# PCB_Reflow_Arduino_V1_0.net
KiCad netlist of a schematic drawn in Altium Designer
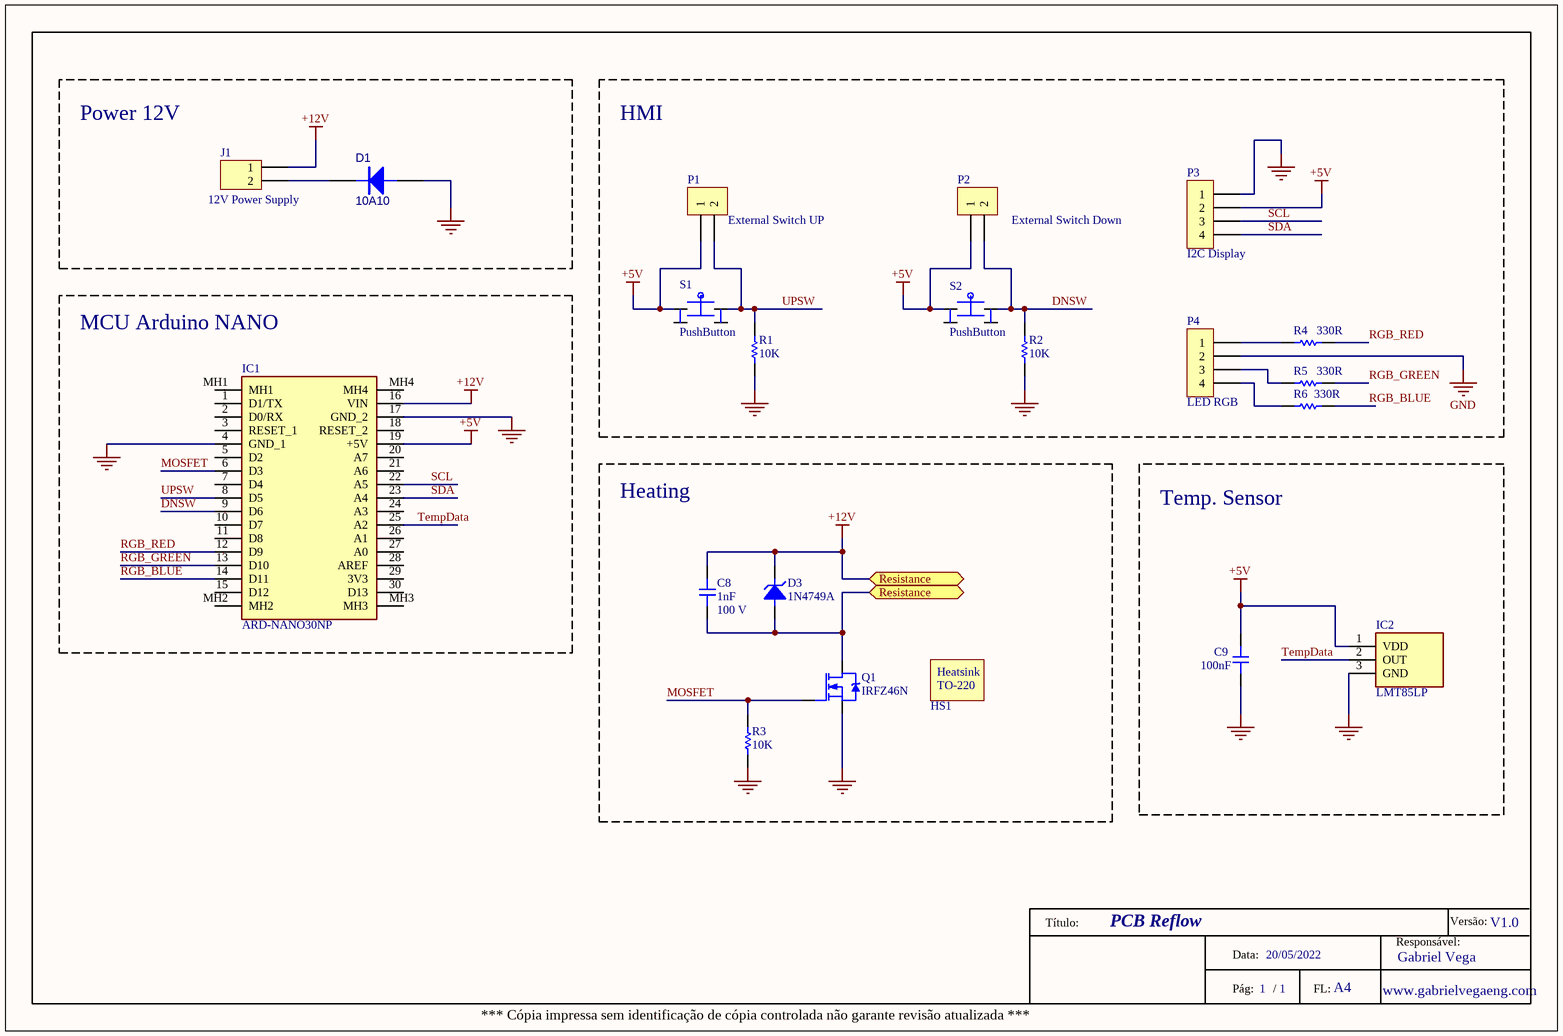
[diagram p0: PCB_Reflow_Arduino_V1.0.SchDoc]

(export (version "E")
  (design (tool "Eeschema 10.0.6"))
  (components
    (comp (ref "C8")
      (value "1nF")
      (footprint "C100-200-100")
      (description "Capacitor")
      (fields (field (name "VOLTAGE") "100 V") (field (name "PUBLISHER") "Altium Limited"))
      (libsource (lib "GPDSE_discrete") (part "Capacitor"))
    )
    (comp (ref "C9")
      (value "100nF")
      (footprint "C100-200-100")
      (description "Capacitor")
      (fields (field (name "VOLTAGE") "100 V") (field (name "PUBLISHER") "Altium Limited"))
      (libsource (lib "GPDSE_discrete") (part "Capacitor"))
    )
    (comp (ref "D1")
      (value "10A10")
      (footprint "DIODE-8.6")
      (description "Diodo")
      (libsource (lib "GPDSE_diode") (part "10A10"))
    )
    (comp (ref "D3")
      (value "1N4749A")
      (footprint "DO-41-Glass")
      (description "Zener Diode")
      (libsource (lib "GPDSE_diode") (part "1N4749A"))
    )
    (comp (ref "HS1")
      (value "HS-TO-220")
      (footprint "HS-TO-220-180847")
      (description "Heatsink TO-220")
      (libsource (lib "GPDSE") (part "HS-TO-220"))
    )
    (comp (ref "IC1")
      (value "ARD-NANO30NP")
      (footprint "SamacSys:ARDNANO30NP")
      (description "Integrated Circuit")
      (fields (field (name "MOUSER PART NUMBER") "992-ARD-NANO30NP"))
      (libsource (lib "*") (part "ARD-NANO30NP"))
    )
    (comp (ref "IC2")
      (value "LMT85LP")
      (footprint "SamacSys:LMT85LP")
      (description "Integrated Circuit")
      (fields (field (name "MOUSER PART NUMBER") "595-LMT85LP"))
      (libsource (lib "*") (part "LMT85LP"))
    )
    (comp (ref "J1")
      (value "12V Power Supply")
      (footprint "PHOENIX_1X2 - 180°")
      (description "Phoenix connector, 1 Lines, 2 Columns, 2 Pins")
      (libsource (lib "GDPSE_connector") (part "Phoenix_1x2"))
    )
    (comp (ref "P1")
      (value "External Switch UP")
      (footprint "HDR-M-1x2-2.54mm-180-9.2mm")
      (description "Header, 1 Line, 2 Columns, 2 Pins")
      (fields (field (name "PUBLISHER") "Altium Limited"))
      (libsource (lib "GDPSE_connector") (part "Header_1x2"))
    )
    (comp (ref "P2")
      (value "External Switch Down")
      (footprint "HDR-M-1x2-2.54mm-180-9.2mm")
      (description "Header, 1 Line, 2 Columns, 2 Pins")
      (fields (field (name "PUBLISHER") "Altium Limited"))
      (libsource (lib "GDPSE_connector") (part "Header_1x2"))
    )
    (comp (ref "P3")
      (value "I2C Display")
      (footprint "HDR-M-1x4-2.54mm-180-9.2mm")
      (description "Header, 1 Line, 4 Columns, 4 Pins")
      (fields (field (name "PUBLISHER") "Altium Limited"))
      (libsource (lib "GDPSE_connector") (part "Header_1x4"))
    )
    (comp (ref "P4")
      (value "LED RGB")
      (footprint "HDR-M-1x4-2.54mm-180-9.2mm")
      (description "Header, 1 Line, 4 Columns, 4 Pins")
      (fields (field (name "PUBLISHER") "Altium Limited"))
      (libsource (lib "GDPSE_connector") (part "Header_1x4"))
    )
    (comp (ref "Q1")
      (value "IRFZ46N")
      (footprint "TO-220/123")
      (description "HEXFET Power MOSFET")
      (libsource (lib "GPDSE") (part "IRFZ46N"))
    )
    (comp (ref "R1")
      (value "10K")
      (footprint "R400-2.0mm")
      (description "Resistor")
      (fields
        (field (name "TOLERANCE") "5%")
        (field (name "POWER") "1/4 W")
        (field (name "PUBLISHER") "Altium Limited")
      )
      (libsource (lib "GPDSE") (part "Resistor"))
    )
    (comp (ref "R2")
      (value "10K")
      (footprint "R400-2.0mm")
      (description "Resistor")
      (fields
        (field (name "TOLERANCE") "5%")
        (field (name "POWER") "1/4 W")
        (field (name "PUBLISHER") "Altium Limited")
      )
      (libsource (lib "GPDSE") (part "Resistor"))
    )
    (comp (ref "R3")
      (value "10K")
      (footprint "R400-2.0mm")
      (description "Resistor")
      (fields
        (field (name "TOLERANCE") "5%")
        (field (name "POWER") "1/4 W")
        (field (name "PUBLISHER") "Altium Limited")
      )
      (libsource (lib "GPDSE") (part "Resistor"))
    )
    (comp (ref "R4")
      (value "330R")
      (footprint "R400-2.0mm")
      (description "Resistor")
      (fields (field (name "TOLERANCE") "5%") (field (name "PUBLISHER") "Altium Limited"))
      (libsource (lib "GPDSE") (part "Resistor"))
    )
    (comp (ref "R5")
      (value "330R")
      (footprint "R400-2.0mm")
      (description "Resistor")
      (fields (field (name "TOLERANCE") "5%") (field (name "PUBLISHER") "Altium Limited"))
      (libsource (lib "GPDSE") (part "Resistor"))
    )
    (comp (ref "R6")
      (value "330R")
      (footprint "R400-2.0mm")
      (description "Resistor")
      (fields (field (name "TOLERANCE") "5%") (field (name "PUBLISHER") "Altium Limited"))
      (libsource (lib "GPDSE") (part "Resistor"))
    )
    (comp (ref "S1")
      (value "PushButton")
      (footprint "DTS-6.0mm-6.0mm-THT")
      (description "Tactile Switch SPST 4 pins")
      (libsource (lib "") (part "PushButton_4_1"))
    )
    (comp (ref "S2")
      (value "PushButton")
      (footprint "DTS-6.0mm-6.0mm-THT")
      (description "Tactile Switch SPST 4 pins")
      (libsource (lib "GPDSE_discrete") (part "PushButton_4"))
    )
  )
  (nets
    (net (code "1") (name "+5V") (class "Default")
      (node (ref "C9") (pin "2") (pinfunction "2_2") (pintype "passive"))
      (node (ref "IC1") (pin "19") (pinfunction "+5V_19") (pintype "passive"))
      (node (ref "IC2") (pin "1") (pinfunction "VDD_1") (pintype "passive"))
      (node (ref "P1") (pin "1") (pinfunction "1_1") (pintype "passive"))
      (node (ref "P2") (pin "1") (pinfunction "1_1") (pintype "passive"))
      (node (ref "P3") (pin "2") (pinfunction "2_2") (pintype "passive"))
      (node (ref "S1") (pin "1") (pinfunction "1_1") (pintype "passive"))
      (node (ref "S2") (pin "1") (pinfunction "1_1") (pintype "passive"))
    )
    (net (code "2") (name "+12V") (class "Default")
      (node (ref "C8") (pin "1") (pinfunction "1_1") (pintype "passive"))
      (node (ref "C8") (pin "2") (pinfunction "2_2") (pintype "passive"))
      (node (ref "D3") (pin "A") (pinfunction "A_A") (pintype "passive"))
      (node (ref "D3") (pin "K") (pinfunction "K_K") (pintype "passive"))
      (node (ref "IC1") (pin "16") (pinfunction "VIN_16") (pintype "passive"))
      (node (ref "J1") (pin "1") (pinfunction "1_1") (pintype "passive"))
      (node (ref "Q1") (pin "D") (pinfunction "D_D") (pintype "passive"))
    )
    (net (code "3") (name "/DNSW") (class "Default")
      (node (ref "IC1") (pin "9") (pinfunction "D6_9") (pintype "passive"))
      (node (ref "P2") (pin "2") (pinfunction "2_2") (pintype "passive"))
      (node (ref "R2") (pin "2") (pinfunction "2_2") (pintype "passive"))
      (node (ref "S2") (pin "3") (pinfunction "3_3") (pintype "passive"))
    )
    (net (code "4") (name "/MOSFET") (class "Default")
      (node (ref "IC1") (pin "6") (pinfunction "D3_6") (pintype "passive"))
      (node (ref "Q1") (pin "G") (pinfunction "G_G") (pintype "passive"))
      (node (ref "R3") (pin "2") (pinfunction "2_2") (pintype "passive"))
    )
    (net (code "5") (name "/RGB_BLUE") (class "Default")
      (node (ref "IC1") (pin "14") (pinfunction "D11_14") (pintype "passive"))
      (node (ref "R6") (pin "1") (pinfunction "1_1") (pintype "passive"))
    )
    (net (code "6") (name "/RGB_GREEN") (class "Default")
      (node (ref "IC1") (pin "13") (pinfunction "D10_13") (pintype "passive"))
      (node (ref "R5") (pin "1") (pinfunction "1_1") (pintype "passive"))
    )
    (net (code "7") (name "/RGB_RED") (class "Default")
      (node (ref "IC1") (pin "12") (pinfunction "D9_12") (pintype "passive"))
      (node (ref "R4") (pin "1") (pinfunction "1_1") (pintype "passive"))
    )
    (net (code "8") (name "/SCL") (class "Default")
      (node (ref "IC1") (pin "22") (pinfunction "A5_22") (pintype "passive"))
      (node (ref "P3") (pin "3") (pinfunction "3_3") (pintype "passive"))
    )
    (net (code "9") (name "/SDA") (class "Default")
      (node (ref "IC1") (pin "23") (pinfunction "A4_23") (pintype "passive"))
      (node (ref "P3") (pin "4") (pinfunction "4_4") (pintype "passive"))
    )
    (net (code "10") (name "/TempData") (class "Default")
      (node (ref "IC1") (pin "25") (pinfunction "A2_25") (pintype "passive"))
      (node (ref "IC2") (pin "2") (pinfunction "OUT_2") (pintype "passive"))
    )
    (net (code "11") (name "/UPSW") (class "Default")
      (node (ref "IC1") (pin "8") (pinfunction "D5_8") (pintype "passive"))
      (node (ref "P1") (pin "2") (pinfunction "2_2") (pintype "passive"))
      (node (ref "R1") (pin "2") (pinfunction "2_2") (pintype "passive"))
      (node (ref "S1") (pin "3") (pinfunction "3_3") (pintype "passive"))
    )
    (net (code "12") (name "GND") (class "Default")
      (node (ref "C9") (pin "1") (pinfunction "1_1") (pintype "passive"))
      (node (ref "D1") (pin "1") (pinfunction "A_1") (pintype "passive"))
      (node (ref "IC1") (pin "17") (pinfunction "GND_2_17") (pintype "passive"))
      (node (ref "IC1") (pin "4") (pinfunction "GND_1_4") (pintype "passive"))
      (node (ref "IC2") (pin "3") (pinfunction "GND_3") (pintype "passive"))
      (node (ref "P3") (pin "1") (pinfunction "1_1") (pintype "passive"))
      (node (ref "P4") (pin "2") (pinfunction "2_2") (pintype "passive"))
      (node (ref "Q1") (pin "S") (pinfunction "S_S") (pintype "passive"))
      (node (ref "R1") (pin "1") (pinfunction "1_1") (pintype "passive"))
      (node (ref "R2") (pin "1") (pinfunction "1_1") (pintype "passive"))
      (node (ref "R3") (pin "1") (pinfunction "1_1") (pintype "passive"))
    )
    (net (code "13") (name "Net-(D1-K)") (class "Default")
      (node (ref "D1") (pin "2") (pinfunction "K_2") (pintype "passive"))
      (node (ref "J1") (pin "2") (pinfunction "2_2") (pintype "passive"))
    )
    (net (code "14") (name "Net-(P4-Pad1)") (class "Default")
      (node (ref "P4") (pin "1") (pinfunction "1_1") (pintype "passive"))
      (node (ref "R4") (pin "2") (pinfunction "2_2") (pintype "passive"))
    )
    (net (code "15") (name "Net-(P4-Pad3)") (class "Default")
      (node (ref "P4") (pin "3") (pinfunction "3_3") (pintype "passive"))
      (node (ref "R5") (pin "2") (pinfunction "2_2") (pintype "passive"))
    )
    (net (code "16") (name "Net-(P4-Pad4)") (class "Default")
      (node (ref "P4") (pin "4") (pinfunction "4_4") (pintype "passive"))
      (node (ref "R6") (pin "2") (pinfunction "2_2") (pintype "passive"))
    )
    (net (code "17") (name "unconnected-(IC1-3V3-Pad29)") (class "Default")
      (node (ref "IC1") (pin "29") (pinfunction "3V3_29") (pintype "passive"))
    )
    (net (code "18") (name "unconnected-(IC1-A0-Pad27)") (class "Default")
      (node (ref "IC1") (pin "27") (pinfunction "A0_27") (pintype "passive"))
    )
    (net (code "19") (name "unconnected-(IC1-A1-Pad26)") (class "Default")
      (node (ref "IC1") (pin "26") (pinfunction "A1_26") (pintype "passive"))
    )
    (net (code "20") (name "unconnected-(IC1-A3-Pad24)") (class "Default")
      (node (ref "IC1") (pin "24") (pinfunction "A3_24") (pintype "passive"))
    )
    (net (code "21") (name "unconnected-(IC1-A6-Pad21)") (class "Default")
      (node (ref "IC1") (pin "21") (pinfunction "A6_21") (pintype "passive"))
    )
    (net (code "22") (name "unconnected-(IC1-A7-Pad20)") (class "Default")
      (node (ref "IC1") (pin "20") (pinfunction "A7_20") (pintype "passive"))
    )
    (net (code "23") (name "unconnected-(IC1-AREF-Pad28)") (class "Default")
      (node (ref "IC1") (pin "28") (pinfunction "AREF_28") (pintype "passive"))
    )
    (net (code "24") (name "unconnected-(IC1-D0{slash}RX-Pad2)") (class "Default")
      (node (ref "IC1") (pin "2") (pinfunction "D0/RX_2") (pintype "passive"))
    )
    (net (code "25") (name "unconnected-(IC1-D1{slash}TX-Pad1)") (class "Default")
      (node (ref "IC1") (pin "1") (pinfunction "D1/TX_1") (pintype "passive"))
    )
    (net (code "26") (name "unconnected-(IC1-D2-Pad5)") (class "Default")
      (node (ref "IC1") (pin "5") (pinfunction "D2_5") (pintype "passive"))
    )
    (net (code "27") (name "unconnected-(IC1-D4-Pad7)") (class "Default")
      (node (ref "IC1") (pin "7") (pinfunction "D4_7") (pintype "passive"))
    )
    (net (code "28") (name "unconnected-(IC1-D7-Pad10)") (class "Default")
      (node (ref "IC1") (pin "10") (pinfunction "D7_10") (pintype "passive"))
    )
    (net (code "29") (name "unconnected-(IC1-D8-Pad11)") (class "Default")
      (node (ref "IC1") (pin "11") (pinfunction "D8_11") (pintype "passive"))
    )
    (net (code "30") (name "unconnected-(IC1-D12-Pad15)") (class "Default")
      (node (ref "IC1") (pin "15") (pinfunction "D12_15") (pintype "passive"))
    )
    (net (code "31") (name "unconnected-(IC1-D13-Pad30)") (class "Default")
      (node (ref "IC1") (pin "30") (pinfunction "D13_30") (pintype "passive"))
    )
    (net (code "32") (name "unconnected-(IC1-PadMH1)") (class "Default")
      (node (ref "IC1") (pin "MH1") (pinfunction "MH1_MH1") (pintype "passive"))
    )
    (net (code "33") (name "unconnected-(IC1-PadMH2)") (class "Default")
      (node (ref "IC1") (pin "MH2") (pinfunction "MH2_MH2") (pintype "passive"))
    )
    (net (code "34") (name "unconnected-(IC1-PadMH3)") (class "Default")
      (node (ref "IC1") (pin "MH3") (pinfunction "MH3_MH3") (pintype "passive"))
    )
    (net (code "35") (name "unconnected-(IC1-PadMH4)") (class "Default")
      (node (ref "IC1") (pin "MH4") (pinfunction "MH4_MH4") (pintype "passive"))
    )
    (net (code "36") (name "unconnected-(IC1-RESET_1-Pad3)") (class "Default")
      (node (ref "IC1") (pin "3") (pinfunction "RESET_1_3") (pintype "passive"))
    )
    (net (code "37") (name "unconnected-(IC1-RESET_2-Pad18)") (class "Default")
      (node (ref "IC1") (pin "18") (pinfunction "RESET_2_18") (pintype "passive"))
    )
    (net (code "38") (name "unconnected-(S1-Pad2)") (class "Default")
      (node (ref "S1") (pin "2") (pinfunction "2_2") (pintype "passive"))
    )
    (net (code "39") (name "unconnected-(S1-Pad4)") (class "Default")
      (node (ref "S1") (pin "4") (pinfunction "4_4") (pintype "passive"))
    )
    (net (code "40") (name "unconnected-(S2-Pad2)") (class "Default")
      (node (ref "S2") (pin "2") (pinfunction "2_2") (pintype "passive"))
    )
    (net (code "41") (name "unconnected-(S2-Pad4)") (class "Default")
      (node (ref "S2") (pin "4") (pinfunction "4_4") (pintype "passive"))
    )
  )
)
